# easyeda-v1-0.net
KiCad netlist of a schematic drawn in EasyEDA
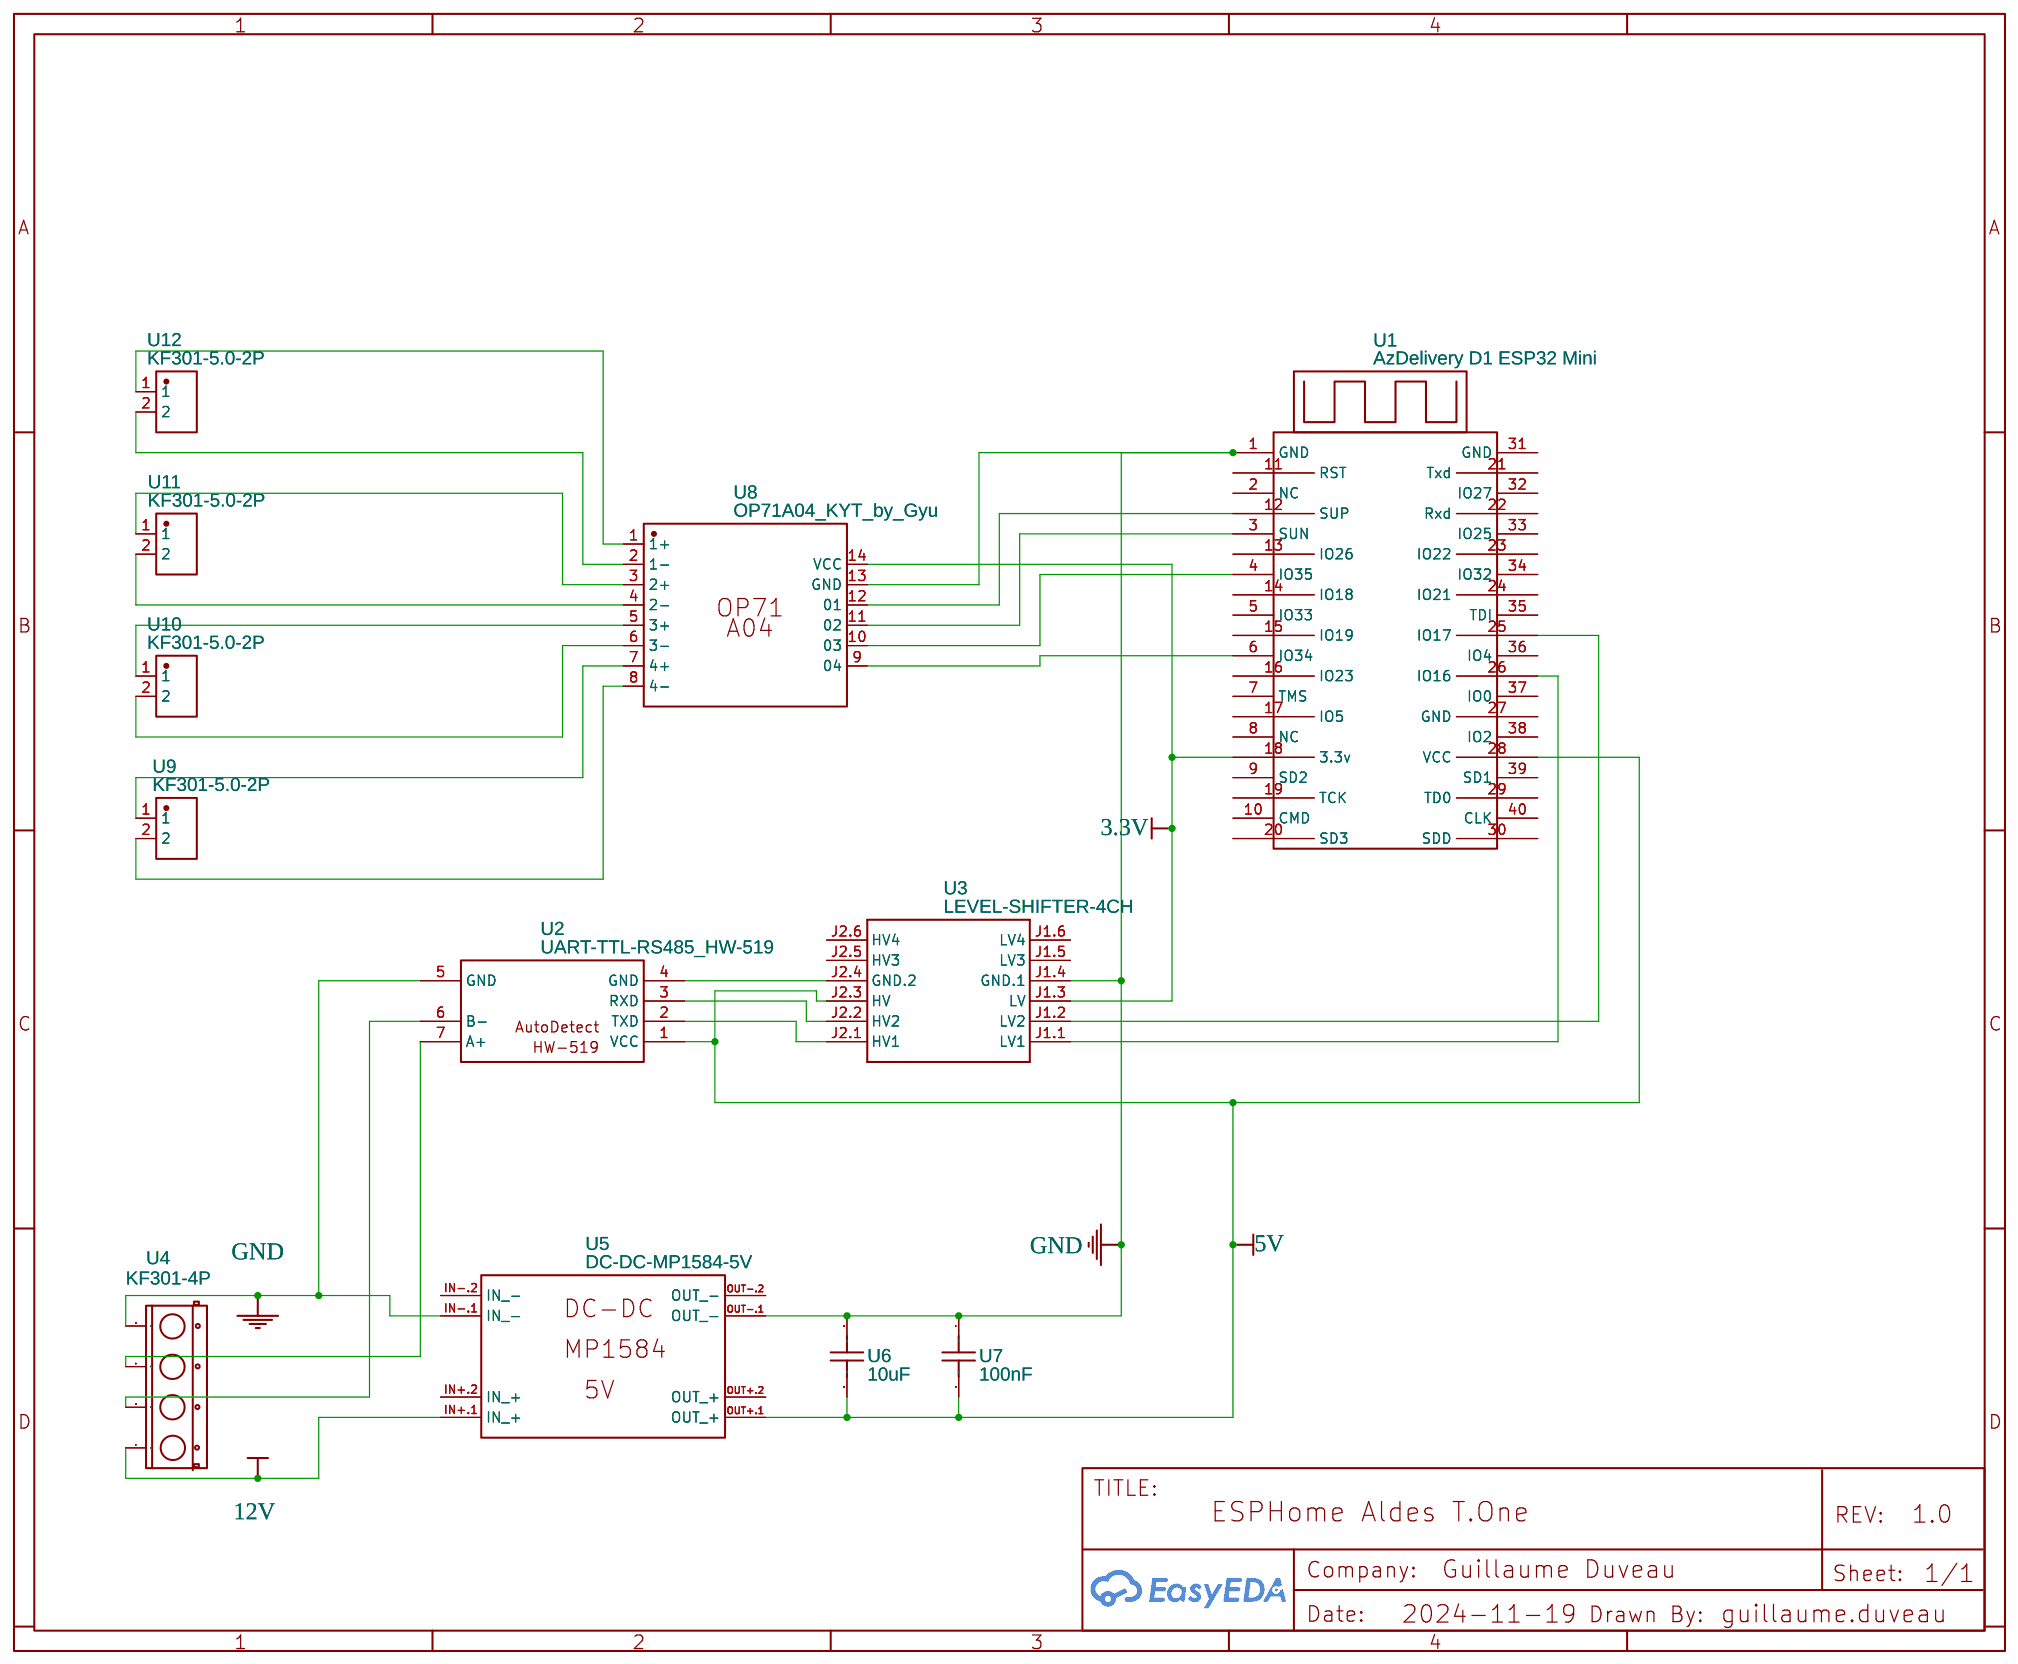
[diagram p0: schematic sheet]

(export (version "E")
  (design (tool "Eeschema 10.0.6"))
  (components
    (comp (ref "U1")
      (value "AzDelivery D1 ESP32 Mini")
      (fields (field (name "Manufacturer Part") "D1 Mini ESP32") (field (name "Manufacturer") "AzDelivery"))
      (libsource (lib "") (part "AzDelivery D1 ESP32 Mini"))
    )
    (comp (ref "U2") (value "UART-TTL-RS485_HW-519") (libsource (lib "") (part "UART-TTL-RS485_HW-519")))
    (comp (ref "U3") (value "LEVEL-SHIFTER-4CH") (libsource (lib "") (part "LEVEL-SHIFTER-4CH")))
    (comp (ref "U4")
      (value "KF301-4P")
      (fields (field (name "Manufacturer Part") "KF301"))
      (libsource (lib "") (part "KF301-4P"))
    )
    (comp (ref "U5") (value "DC-DC-MP1584-5V") (libsource (lib "") (part "DC-DC-MP1584-5V")))
    (comp (ref "U6")
      (value "10uF")
      (fields
        (field (name "Manufacturer Part") "TMK316AB7106KLHT")
        (field (name "Manufacturer") "TAIYO YUDEN(太诱)")
      )
      (libsource (lib "") (part "TMK316AB7106KLHT_C20505300"))
    )
    (comp (ref "U7")
      (value "100nF")
      (fields
        (field (name "Manufacturer Part") "GA1206H104MBXBR31G")
        (field (name "Manufacturer") "VISHAY(威世)")
      )
      (libsource (lib "") (part "GA1206H104MBXBR31G"))
    )
    (comp (ref "U8") (value "OP71A04_KYT_by_Gyu") (libsource (lib "") (part "OP71A04_KYT_by_Gyu")))
    (comp (ref "U9")
      (value "KF301-5.0-2P")
      (fields (field (name "Manufacturer") "KEFA(科发)"))
      (libsource (lib "") (part "KF301-5.0-2P"))
    )
    (comp (ref "U10")
      (value "KF301-5.0-2P")
      (fields (field (name "Manufacturer") "KEFA(科发)"))
      (libsource (lib "") (part "KF301-5.0-2P"))
    )
    (comp (ref "U11")
      (value "KF301-5.0-2P")
      (fields (field (name "Manufacturer") "KEFA(科发)"))
      (libsource (lib "") (part "KF301-5.0-2P"))
    )
    (comp (ref "U12")
      (value "KF301-5.0-2P")
      (fields (field (name "Manufacturer") "KEFA(科发)"))
      (libsource (lib "") (part "KF301-5.0-2P"))
    )
  )
  (nets
    (net (code "1") (name "3.3V") (class "Default")
      (node (ref "U1") (pin "18") (pinfunction "3.3v_18") (pintype "unspecified"))
      (node (ref "U3") (pin "J1.3") (pinfunction "LV_J1.3") (pintype "bidirectional"))
      (node (ref "U8") (pin "14") (pinfunction "VCC_14") (pintype "unspecified"))
    )
    (net (code "2") (name "5V") (class "Default")
      (node (ref "U1") (pin "28") (pinfunction "VCC_28") (pintype "unspecified"))
      (node (ref "U2") (pin "1") (pinfunction "VCC_1") (pintype "unspecified"))
      (node (ref "U3") (pin "J2.3") (pinfunction "HV_J2.3") (pintype "bidirectional"))
      (node (ref "U5") (pin "OUT+.1") (pinfunction "OUT_+_OUT+.1") (pintype "unspecified"))
      (node (ref "U6") (pin "2") (pinfunction "2_2") (pintype "unspecified"))
      (node (ref "U7") (pin "2") (pinfunction "2_2") (pintype "unspecified"))
    )
    (net (code "3") (name "12V") (class "Default")
      (node (ref "U4") (pin "4") (pinfunction "4_4") (pintype "unspecified"))
      (node (ref "U5") (pin "IN+.1") (pinfunction "IN_+_IN+.1") (pintype "unspecified"))
    )
    (net (code "4") (name "GND") (class "Default")
      (node (ref "U1") (pin "1") (pinfunction "GND_1") (pintype "unspecified"))
      (node (ref "U2") (pin "5") (pinfunction "GND_5") (pintype "unspecified"))
      (node (ref "U3") (pin "J1.4") (pinfunction "GND.1_J1.4") (pintype "bidirectional"))
      (node (ref "U4") (pin "1") (pinfunction "1_1") (pintype "unspecified"))
      (node (ref "U5") (pin "IN-.1") (pinfunction "IN_-_IN-.1") (pintype "unspecified"))
      (node (ref "U5") (pin "OUT-.1") (pinfunction "OUT_-_OUT-.1") (pintype "unspecified"))
      (node (ref "U6") (pin "1") (pinfunction "1_1") (pintype "unspecified"))
      (node (ref "U7") (pin "1") (pinfunction "1_1") (pintype "unspecified"))
      (node (ref "U8") (pin "13") (pinfunction "GND_13") (pintype "unspecified"))
    )
    (net (code "5") (name "Net-(U1-IO16)") (class "Default")
      (node (ref "U1") (pin "26") (pinfunction "IO16_26") (pintype "unspecified"))
      (node (ref "U3") (pin "J1.1") (pinfunction "LV1_J1.1") (pintype "bidirectional"))
    )
    (net (code "6") (name "Net-(U1-IO17)") (class "Default")
      (node (ref "U1") (pin "25") (pinfunction "IO17_25") (pintype "unspecified"))
      (node (ref "U3") (pin "J1.2") (pinfunction "LV2_J1.2") (pintype "bidirectional"))
    )
    (net (code "7") (name "Net-(U1-IO34)") (class "Default")
      (node (ref "U1") (pin "6") (pinfunction "IO34_6") (pintype "unspecified"))
      (node (ref "U8") (pin "9") (pinfunction "04_9") (pintype "unspecified"))
    )
    (net (code "8") (name "Net-(U1-IO35)") (class "Default")
      (node (ref "U1") (pin "4") (pinfunction "IO35_4") (pintype "unspecified"))
      (node (ref "U8") (pin "10") (pinfunction "03_10") (pintype "unspecified"))
    )
    (net (code "9") (name "Net-(U1-SUN)") (class "Default")
      (node (ref "U1") (pin "3") (pinfunction "SUN_3") (pintype "unspecified"))
      (node (ref "U8") (pin "11") (pinfunction "02_11") (pintype "unspecified"))
    )
    (net (code "10") (name "Net-(U1-SUP)") (class "Default")
      (node (ref "U1") (pin "12") (pinfunction "SUP_12") (pintype "unspecified"))
      (node (ref "U8") (pin "12") (pinfunction "01_12") (pintype "unspecified"))
    )
    (net (code "11") (name "Net-(U2-A+)") (class "Default")
      (node (ref "U2") (pin "7") (pinfunction "A+_7") (pintype "unspecified"))
      (node (ref "U4") (pin "2") (pinfunction "2_2") (pintype "unspecified"))
    )
    (net (code "12") (name "Net-(U2-B-)") (class "Default")
      (node (ref "U2") (pin "6") (pinfunction "B-_6") (pintype "unspecified"))
      (node (ref "U4") (pin "3") (pinfunction "3_3") (pintype "unspecified"))
    )
    (net (code "13") (name "Net-(U2-RXD)") (class "Default")
      (node (ref "U2") (pin "3") (pinfunction "RXD_3") (pintype "unspecified"))
      (node (ref "U3") (pin "J2.2") (pinfunction "HV2_J2.2") (pintype "bidirectional"))
    )
    (net (code "14") (name "Net-(U2-TXD)") (class "Default")
      (node (ref "U2") (pin "2") (pinfunction "TXD_2") (pintype "unspecified"))
      (node (ref "U3") (pin "J2.1") (pinfunction "HV1_J2.1") (pintype "bidirectional"))
    )
    (net (code "15") (name "Net-(U3-GND.2)") (class "Default")
      (node (ref "U2") (pin "4") (pinfunction "GND_4") (pintype "unspecified"))
      (node (ref "U3") (pin "J2.4") (pinfunction "GND.2_J2.4") (pintype "bidirectional"))
    )
    (net (code "16") (name "Net-(U8-1+)") (class "Default")
      (node (ref "U12") (pin "1") (pinfunction "1_1") (pintype "unspecified"))
      (node (ref "U8") (pin "1") (pinfunction "1+_1") (pintype "unspecified"))
    )
    (net (code "17") (name "Net-(U8-1-)") (class "Default")
      (node (ref "U12") (pin "2") (pinfunction "2_2") (pintype "unspecified"))
      (node (ref "U8") (pin "2") (pinfunction "1-_2") (pintype "unspecified"))
    )
    (net (code "18") (name "Net-(U8-2+)") (class "Default")
      (node (ref "U11") (pin "1") (pinfunction "1_1") (pintype "unspecified"))
      (node (ref "U8") (pin "3") (pinfunction "2+_3") (pintype "unspecified"))
    )
    (net (code "19") (name "Net-(U8-2-)") (class "Default")
      (node (ref "U11") (pin "2") (pinfunction "2_2") (pintype "unspecified"))
      (node (ref "U8") (pin "4") (pinfunction "2-_4") (pintype "unspecified"))
    )
    (net (code "20") (name "Net-(U8-3+)") (class "Default")
      (node (ref "U10") (pin "1") (pinfunction "1_1") (pintype "unspecified"))
      (node (ref "U8") (pin "5") (pinfunction "3+_5") (pintype "unspecified"))
    )
    (net (code "21") (name "Net-(U8-3-)") (class "Default")
      (node (ref "U10") (pin "2") (pinfunction "2_2") (pintype "unspecified"))
      (node (ref "U8") (pin "6") (pinfunction "3-_6") (pintype "unspecified"))
    )
    (net (code "22") (name "Net-(U8-4+)") (class "Default")
      (node (ref "U8") (pin "7") (pinfunction "4+_7") (pintype "unspecified"))
      (node (ref "U9") (pin "1") (pinfunction "1_1") (pintype "unspecified"))
    )
    (net (code "23") (name "Net-(U8-4-)") (class "Default")
      (node (ref "U8") (pin "8") (pinfunction "4-_8") (pintype "unspecified"))
      (node (ref "U9") (pin "2") (pinfunction "2_2") (pintype "unspecified"))
    )
    (net (code "24") (name "unconnected-(U1-CLK-Pad40)") (class "Default")
      (node (ref "U1") (pin "40") (pinfunction "CLK_40") (pintype "unspecified"))
    )
    (net (code "25") (name "unconnected-(U1-CMD-Pad10)") (class "Default")
      (node (ref "U1") (pin "10") (pinfunction "CMD_10") (pintype "unspecified"))
    )
    (net (code "26") (name "unconnected-(U1-GND-Pad27)") (class "Default")
      (node (ref "U1") (pin "27") (pinfunction "GND_27") (pintype "unspecified"))
    )
    (net (code "27") (name "unconnected-(U1-GND-Pad31)") (class "Default")
      (node (ref "U1") (pin "31") (pinfunction "GND_31") (pintype "unspecified"))
    )
    (net (code "28") (name "unconnected-(U1-IO0-Pad37)") (class "Default")
      (node (ref "U1") (pin "37") (pinfunction "IO0_37") (pintype "unspecified"))
    )
    (net (code "29") (name "unconnected-(U1-IO2-Pad38)") (class "Default")
      (node (ref "U1") (pin "38") (pinfunction "IO2_38") (pintype "unspecified"))
    )
    (net (code "30") (name "unconnected-(U1-IO4-Pad36)") (class "Default")
      (node (ref "U1") (pin "36") (pinfunction "IO4_36") (pintype "unspecified"))
    )
    (net (code "31") (name "unconnected-(U1-IO5-Pad17)") (class "Default")
      (node (ref "U1") (pin "17") (pinfunction "IO5_17") (pintype "unspecified"))
    )
    (net (code "32") (name "unconnected-(U1-IO18-Pad14)") (class "Default")
      (node (ref "U1") (pin "14") (pinfunction "IO18_14") (pintype "unspecified"))
    )
    (net (code "33") (name "unconnected-(U1-IO19-Pad15)") (class "Default")
      (node (ref "U1") (pin "15") (pinfunction "IO19_15") (pintype "unspecified"))
    )
    (net (code "34") (name "unconnected-(U1-IO21-Pad24)") (class "Default")
      (node (ref "U1") (pin "24") (pinfunction "IO21_24") (pintype "unspecified"))
    )
    (net (code "35") (name "unconnected-(U1-IO22-Pad23)") (class "Default")
      (node (ref "U1") (pin "23") (pinfunction "IO22_23") (pintype "unspecified"))
    )
    (net (code "36") (name "unconnected-(U1-IO23-Pad16)") (class "Default")
      (node (ref "U1") (pin "16") (pinfunction "IO23_16") (pintype "unspecified"))
    )
    (net (code "37") (name "unconnected-(U1-IO25-Pad33)") (class "Default")
      (node (ref "U1") (pin "33") (pinfunction "IO25_33") (pintype "unspecified"))
    )
    (net (code "38") (name "unconnected-(U1-IO26-Pad13)") (class "Default")
      (node (ref "U1") (pin "13") (pinfunction "IO26_13") (pintype "unspecified"))
    )
    (net (code "39") (name "unconnected-(U1-IO27-Pad32)") (class "Default")
      (node (ref "U1") (pin "32") (pinfunction "IO27_32") (pintype "unspecified"))
    )
    (net (code "40") (name "unconnected-(U1-IO32-Pad34)") (class "Default")
      (node (ref "U1") (pin "34") (pinfunction "IO32_34") (pintype "unspecified"))
    )
    (net (code "41") (name "unconnected-(U1-IO33-Pad5)") (class "Default")
      (node (ref "U1") (pin "5") (pinfunction "IO33_5") (pintype "unspecified"))
    )
    (net (code "42") (name "unconnected-(U1-NC-Pad2)") (class "Default")
      (node (ref "U1") (pin "2") (pinfunction "NC_2") (pintype "unspecified"))
    )
    (net (code "43") (name "unconnected-(U1-NC-Pad8)") (class "Default")
      (node (ref "U1") (pin "8") (pinfunction "NC_8") (pintype "unspecified"))
    )
    (net (code "44") (name "unconnected-(U1-RST-Pad11)") (class "Default")
      (node (ref "U1") (pin "11") (pinfunction "RST_11") (pintype "unspecified"))
    )
    (net (code "45") (name "unconnected-(U1-Rxd-Pad22)") (class "Default")
      (node (ref "U1") (pin "22") (pinfunction "Rxd_22") (pintype "unspecified"))
    )
    (net (code "46") (name "unconnected-(U1-SD1-Pad39)") (class "Default")
      (node (ref "U1") (pin "39") (pinfunction "SD1_39") (pintype "unspecified"))
    )
    (net (code "47") (name "unconnected-(U1-SD2-Pad9)") (class "Default")
      (node (ref "U1") (pin "9") (pinfunction "SD2_9") (pintype "unspecified"))
    )
    (net (code "48") (name "unconnected-(U1-SD3-Pad20)") (class "Default")
      (node (ref "U1") (pin "20") (pinfunction "SD3_20") (pintype "unspecified"))
    )
    (net (code "49") (name "unconnected-(U1-SDD-Pad30)") (class "Default")
      (node (ref "U1") (pin "30") (pinfunction "SDD_30") (pintype "unspecified"))
    )
    (net (code "50") (name "unconnected-(U1-TCK-Pad19)") (class "Default")
      (node (ref "U1") (pin "19") (pinfunction "TCK_19") (pintype "unspecified"))
    )
    (net (code "51") (name "unconnected-(U1-TD0-Pad29)") (class "Default")
      (node (ref "U1") (pin "29") (pinfunction "TD0_29") (pintype "unspecified"))
    )
    (net (code "52") (name "unconnected-(U1-TDI-Pad35)") (class "Default")
      (node (ref "U1") (pin "35") (pinfunction "TDI_35") (pintype "unspecified"))
    )
    (net (code "53") (name "unconnected-(U1-TMS-Pad7)") (class "Default")
      (node (ref "U1") (pin "7") (pinfunction "TMS_7") (pintype "unspecified"))
    )
    (net (code "54") (name "unconnected-(U1-Txd-Pad21)") (class "Default")
      (node (ref "U1") (pin "21") (pinfunction "Txd_21") (pintype "unspecified"))
    )
    (net (code "55") (name "unconnected-(U3-HV3-PadJ2.5)") (class "Default")
      (node (ref "U3") (pin "J2.5") (pinfunction "HV3_J2.5") (pintype "bidirectional"))
    )
    (net (code "56") (name "unconnected-(U3-HV4-PadJ2.6)") (class "Default")
      (node (ref "U3") (pin "J2.6") (pinfunction "HV4_J2.6") (pintype "bidirectional"))
    )
    (net (code "57") (name "unconnected-(U3-LV3-PadJ1.5)") (class "Default")
      (node (ref "U3") (pin "J1.5") (pinfunction "LV3_J1.5") (pintype "bidirectional"))
    )
    (net (code "58") (name "unconnected-(U3-LV4-PadJ1.6)") (class "Default")
      (node (ref "U3") (pin "J1.6") (pinfunction "LV4_J1.6") (pintype "bidirectional"))
    )
    (net (code "59") (name "unconnected-(U5-IN_+-PadIN+.2)") (class "Default")
      (node (ref "U5") (pin "IN+.2") (pinfunction "IN_+_IN+.2") (pintype "unspecified"))
    )
    (net (code "60") (name "unconnected-(U5-IN_--PadIN-.2)") (class "Default")
      (node (ref "U5") (pin "IN-.2") (pinfunction "IN_-_IN-.2") (pintype "unspecified"))
    )
    (net (code "61") (name "unconnected-(U5-OUT_+-PadOUT+.2)") (class "Default")
      (node (ref "U5") (pin "OUT+.2") (pinfunction "OUT_+_OUT+.2") (pintype "unspecified"))
    )
    (net (code "62") (name "unconnected-(U5-OUT_--PadOUT-.2)") (class "Default")
      (node (ref "U5") (pin "OUT-.2") (pinfunction "OUT_-_OUT-.2") (pintype "unspecified"))
    )
  )
)
